# Amplificador.net
KiCad netlist of a schematic drawn in EAGLE
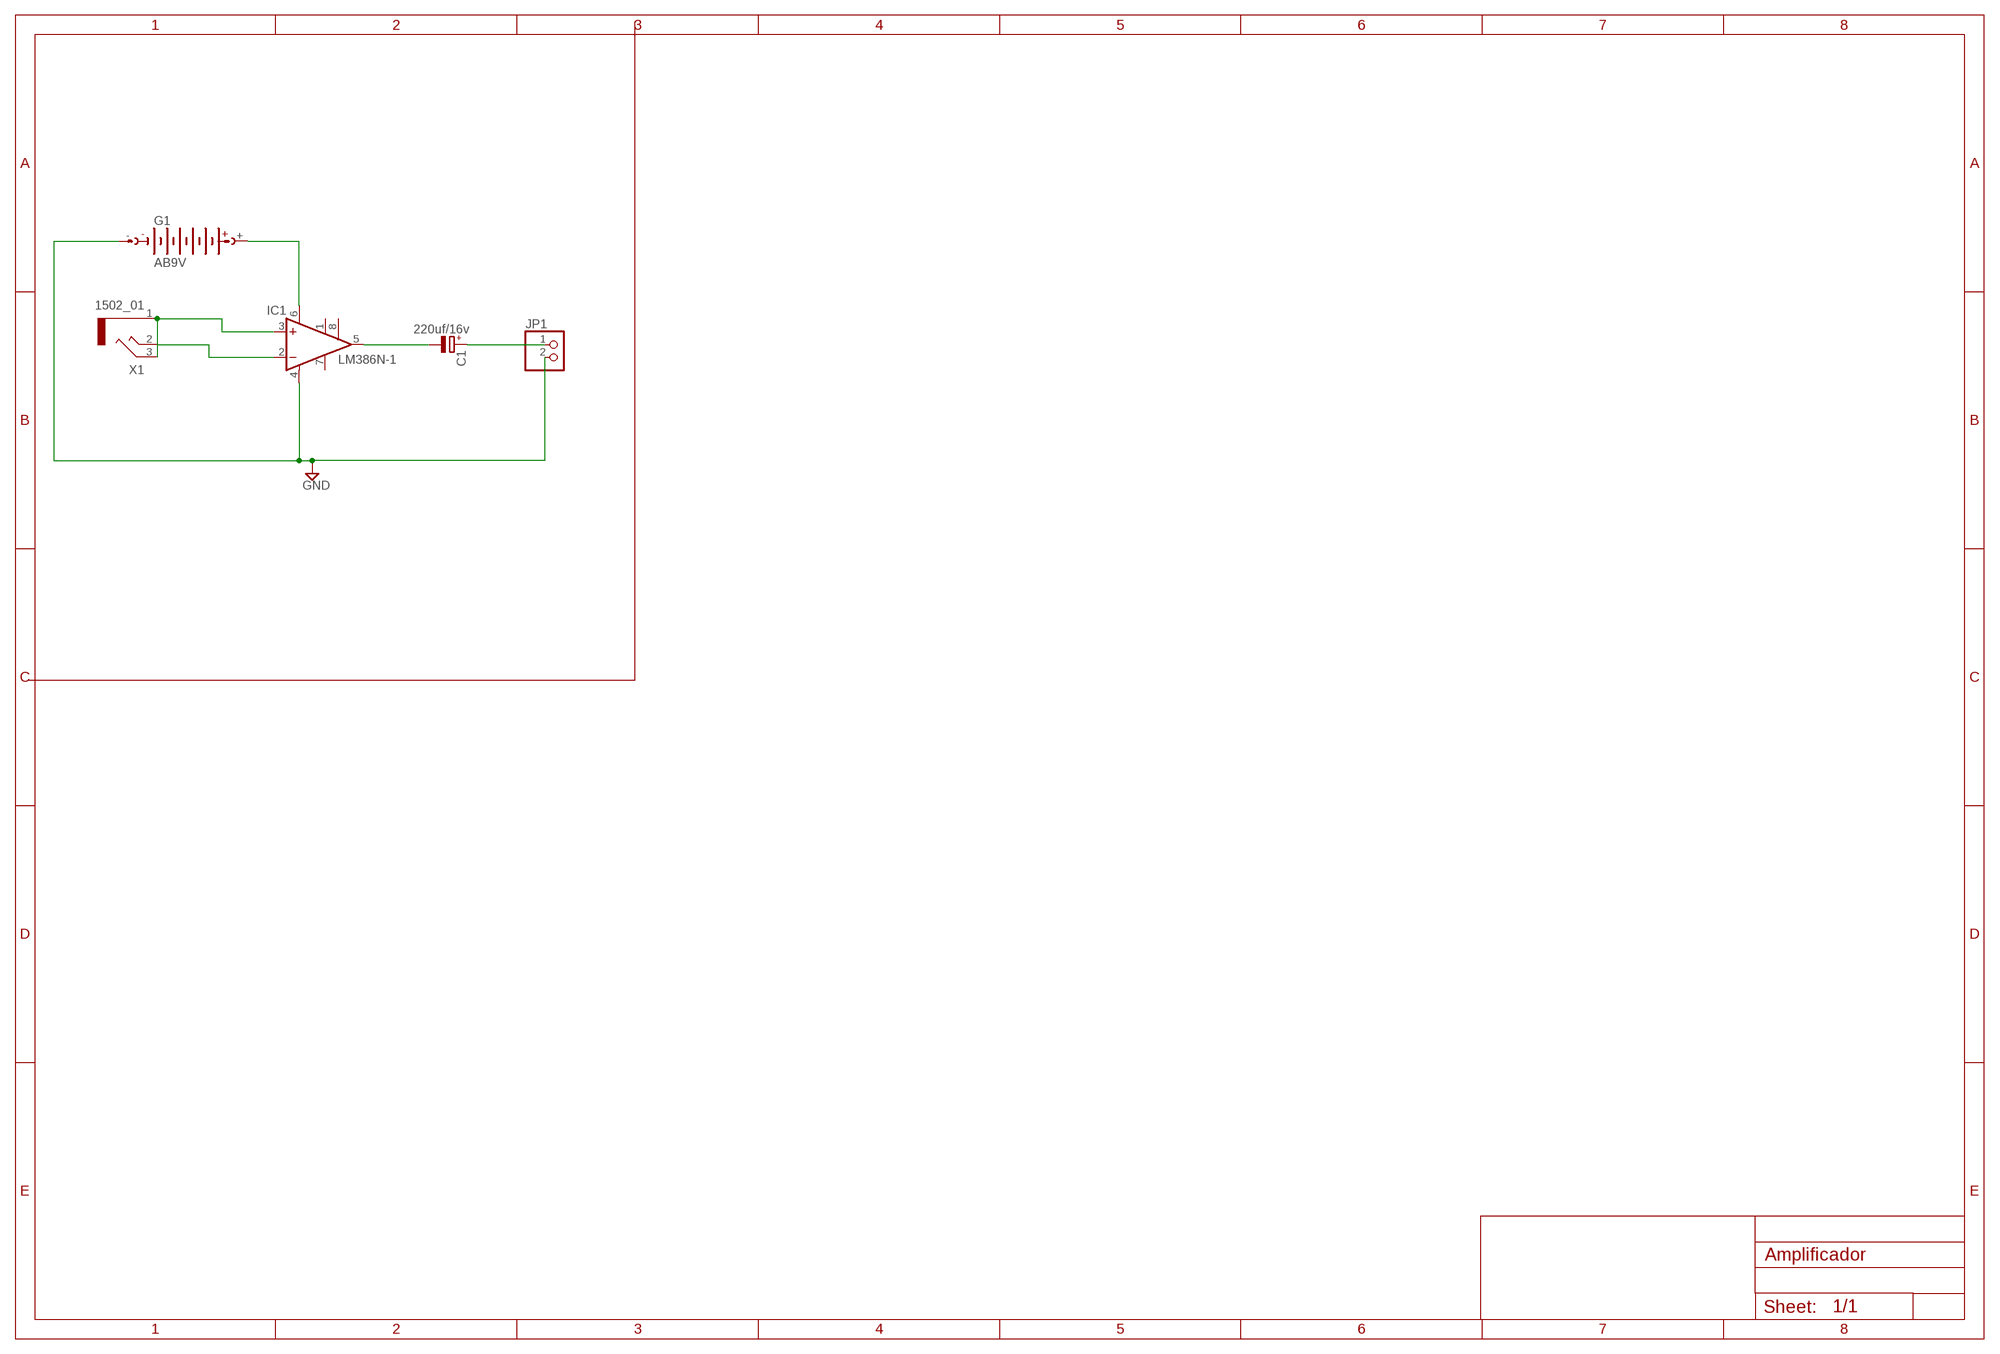
[diagram p0: schematic, sheet 1]

(export (version "E")
  (design (tool "Eeschema 10.0.6"))
  (components
    (comp (ref "C1")
      (value "220uf/16v")
      (footprint "eagle-import:E3,5-8")
      (libsource (lib "eagle-import") (part "CPOL-EUE3.5-8"))
    )
    (comp (ref "G1")
      (value "AB9V")
      (footprint "eagle-import:AB9V")
      (libsource (lib "eagle-import") (part "AB9V"))
    )
    (comp (ref "IC1")
      (value "LM386N-1")
      (footprint "eagle-import:DIL08")
      (libsource (lib "eagle-import") (part "LM386?-N1"))
    )
    (comp (ref "JP1")
      (value "PINHD-1X2")
      (footprint "eagle-import:1X02")
      (libsource (lib "eagle-import") (part "PINHD-1X2"))
    )
    (comp (ref "X1")
      (value "1502_01")
      (footprint "eagle-import:1502_01")
      (libsource (lib "eagle-import") (part "1502_01"))
    )
  )
  (nets
    (net (code "1") (name "GND") (class "Default")
      (node (ref "G1") (pin "-") (pinfunction "-_-") (pintype "passive"))
      (node (ref "IC1") (pin "4") (pinfunction "GND_4") (pintype "power_in"))
      (node (ref "JP1") (pin "2") (pinfunction "2_2") (pintype "passive"))
    )
    (net (code "2") (name "Net-(C1-Pad+)") (class "Default")
      (node (ref "C1") (pin "+") (pinfunction "+_+") (pintype "passive"))
      (node (ref "JP1") (pin "1") (pinfunction "1_1") (pintype "passive"))
    )
    (net (code "3") (name "Net-(IC1-+IN)") (class "Default")
      (node (ref "IC1") (pin "3") (pinfunction "+IN_3") (pintype "input"))
      (node (ref "X1") (pin "1") (pinfunction "1_1") (pintype "passive"))
      (node (ref "X1") (pin "3") (pinfunction "2_3") (pintype "passive"))
    )
    (net (code "4") (name "Net-(IC1--IN)") (class "Default")
      (node (ref "IC1") (pin "2") (pinfunction "-IN_2") (pintype "input"))
      (node (ref "X1") (pin "2") (pinfunction "3_2") (pintype "passive"))
    )
    (net (code "5") (name "Net-(IC1-OUT)") (class "Default")
      (node (ref "C1") (pin "-") (pinfunction "-_-") (pintype "passive"))
      (node (ref "IC1") (pin "5") (pinfunction "OUT_5") (pintype "output"))
    )
    (net (code "6") (name "Net-(IC1-VS)") (class "Default")
      (node (ref "G1") (pin "+") (pinfunction "+_+") (pintype "passive"))
      (node (ref "IC1") (pin "6") (pinfunction "VS_6") (pintype "power_in"))
    )
    (net (code "7") (name "unconnected-(IC1-BYPASS-Pad7)") (class "Default")
      (node (ref "IC1") (pin "7") (pinfunction "BYPASS_7") (pintype "passive"))
    )
    (net (code "8") (name "unconnected-(IC1-GAIN-Pad1)") (class "Default")
      (node (ref "IC1") (pin "1") (pinfunction "GAIN_1") (pintype "passive"))
    )
    (net (code "9") (name "unconnected-(IC1-GAIN-Pad8)") (class "Default")
      (node (ref "IC1") (pin "8") (pinfunction "GAIN_8") (pintype "passive"))
    )
  )
)
